# Decawave.net
KiCad netlist of a schematic drawn in Altium Designer
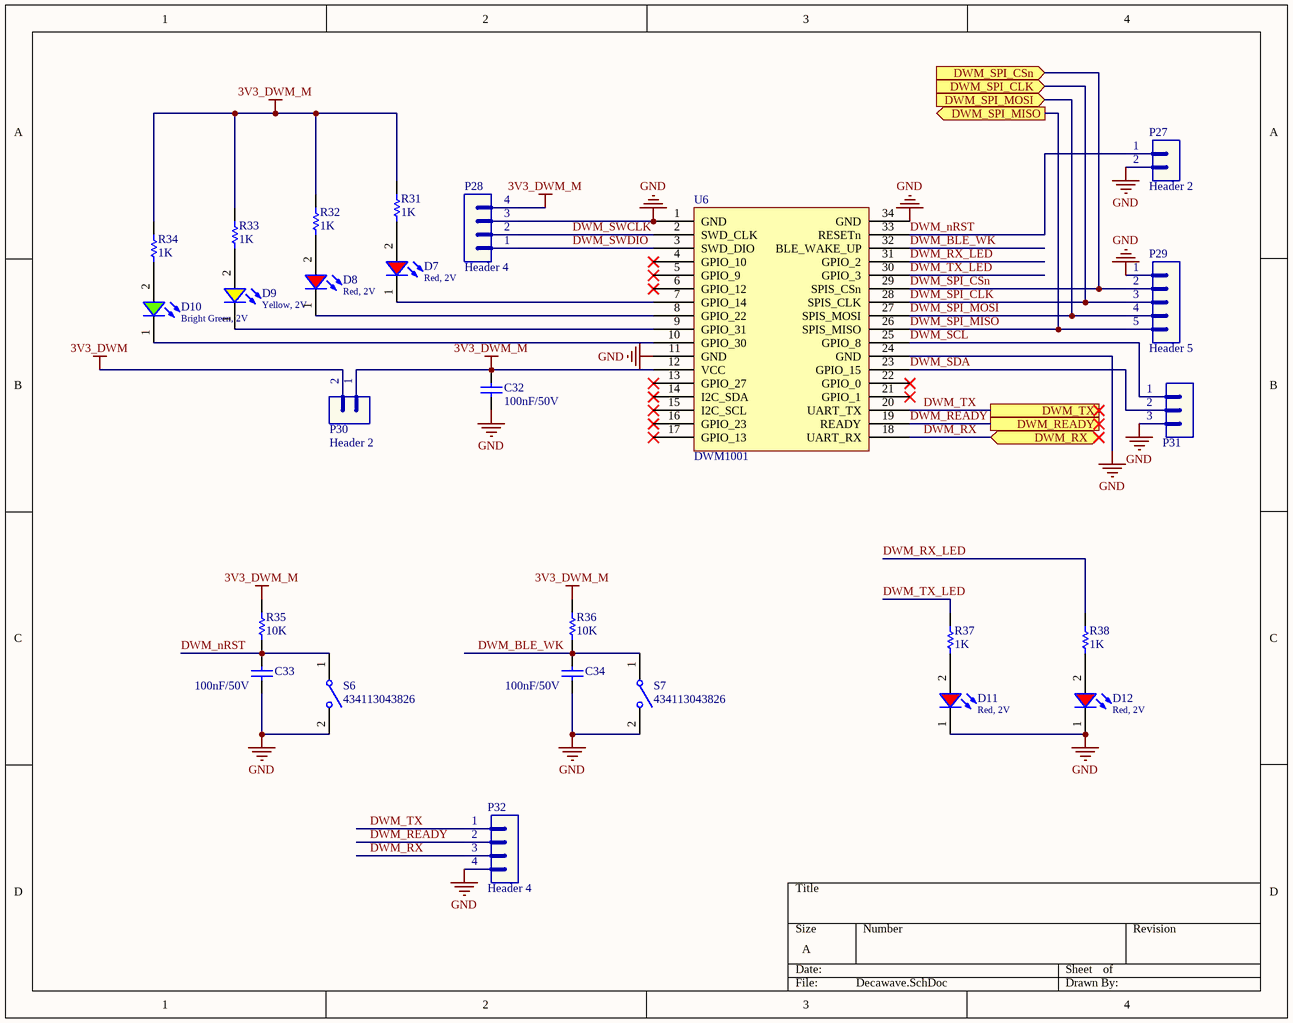
[diagram p0: Decawave.SchDoc]

(export (version "E")
  (design (tool "Eeschema 10.0.6"))
  (components
    (comp (ref "C32")
      (value "100nF/50V")
      (footprint "CAP-SM-0805")
      (description "CAP CER 0.1UF 50V Y5V 0805")
      (fields
        (field (name "MANUFACTURER") "Samsung Electro-Mechanics")
        (field (name "MANUFACTURER PART NUMBER") "CL21F104ZBCNNNC")
      )
      (libsource (lib "Capacitor") (part "Cap-100nF-50V-0805"))
    )
    (comp (ref "C33")
      (value "100nF/50V")
      (footprint "CAP-SM-0805")
      (description "CAP CER 0.1UF 50V Y5V 0805")
      (fields
        (field (name "MANUFACTURER") "Samsung Electro-Mechanics")
        (field (name "MANUFACTURER PART NUMBER") "CL21F104ZBCNNNC")
      )
      (libsource (lib "Capacitor") (part "Cap-100nF-50V-0805"))
    )
    (comp (ref "C34")
      (value "100nF/50V")
      (footprint "CAP-SM-0805")
      (description "CAP CER 0.1UF 50V Y5V 0805")
      (fields
        (field (name "MANUFACTURER") "Samsung Electro-Mechanics")
        (field (name "MANUFACTURER PART NUMBER") "CL21F104ZBCNNNC")
      )
      (libsource (lib "Capacitor") (part "Cap-100nF-50V-0805"))
    )
    (comp (ref "D7")
      (value "Red, 2V")
      (footprint "WL-SMCW_0805")
      (description "WL-SMCW SMT Mono-color Chip LED Waterclear, size 0805, Red, 2V, 140deg")
      (fields (field (name "PART NUMBER") "150080RS75000") (field (name "PUBLISHER") "Wurth Elektronik"))
      (libsource (lib "LED_150060BS75000_Altium_WL-SMCW_rev20a") (part "150080RS75000"))
    )
    (comp (ref "D8")
      (value "Red, 2V")
      (footprint "WL-SMCW_0805")
      (description "WL-SMCW SMT Mono-color Chip LED Waterclear, size 0805, Red, 2V, 140deg")
      (fields (field (name "PART NUMBER") "150080RS75000") (field (name "PUBLISHER") "Wurth Elektronik"))
      (libsource (lib "LED_150060BS75000_Altium_WL-SMCW_rev20a") (part "150080RS75000"))
    )
    (comp (ref "D9")
      (value "Yellow, 2V")
      (footprint "WL-SMCW_0805")
      (description "WL-SMCW SMT Mono-color Chip LED Waterclear, size 0805, Yellow, 2V, 140deg")
      (fields (field (name "PART NUMBER") "150080YS75000") (field (name "PUBLISHER") "Wurth Elektronik"))
      (libsource (lib "LED_150060BS75000_Altium_WL-SMCW_rev20a") (part "150080YS75000"))
    )
    (comp (ref "D10")
      (value "Bright Green, 2V")
      (footprint "WL-SMCW_0805")
      (description "WL-SMCW SMT Mono-color Chip LED Waterclear, size 0805, Bright Green, 2V, 140deg")
      (fields (field (name "PART NUMBER") "150080VS75000") (field (name "PUBLISHER") "Wurth Elektronik"))
      (libsource (lib "LED_150060BS75000_Altium_WL-SMCW_rev20a") (part "150080VS75000"))
    )
    (comp (ref "D11")
      (value "Red, 2V")
      (footprint "WL-SMCW_0805")
      (description "WL-SMCW SMT Mono-color Chip LED Waterclear, size 0805, Red, 2V, 140deg")
      (fields (field (name "PART NUMBER") "150080RS75000") (field (name "PUBLISHER") "Wurth Elektronik"))
      (libsource (lib "LED_150060BS75000_Altium_WL-SMCW_rev20a") (part "150080RS75000"))
    )
    (comp (ref "D12")
      (value "Red, 2V")
      (footprint "WL-SMCW_0805")
      (description "WL-SMCW SMT Mono-color Chip LED Waterclear, size 0805, Red, 2V, 140deg")
      (fields (field (name "PART NUMBER") "150080RS75000") (field (name "PUBLISHER") "Wurth Elektronik"))
      (libsource (lib "LED_150060BS75000_Altium_WL-SMCW_rev20a") (part "150080RS75000"))
    )
    (comp (ref "P27")
      (value "Header 2")
      (footprint "JP2")
      (description "Header, 2-Pin")
      (fields (field (name "PUBLISHER") "Altium Limited"))
      (libsource (lib "") (part "Header 2_1"))
    )
    (comp (ref "P28")
      (value "Header 4")
      (footprint "JP4")
      (description "Header, 4-Pin")
      (fields (field (name "PUBLISHER") "Altium Limited"))
      (libsource (lib "Header-connector") (part "Header 4"))
    )
    (comp (ref "P29")
      (value "Header 5")
      (footprint "JP5")
      (description "Header, 5-Pin")
      (fields (field (name "PUBLISHER") "Altium Limited"))
      (libsource (lib "Header-connector") (part "Header 5"))
    )
    (comp (ref "P30")
      (value "Header 2")
      (footprint "JP2")
      (description "Header, 2-Pin")
      (fields (field (name "PUBLISHER") "Altium Limited"))
      (libsource (lib "Header-connector") (part "Header 2"))
    )
    (comp (ref "P31")
      (value "Header 3")
      (footprint "JP3")
      (description "Header, 3-Pin")
      (fields (field (name "PUBLISHER") "Altium Limited"))
      (libsource (lib "Header-connector") (part "Header 3"))
    )
    (comp (ref "P32")
      (value "Header 4")
      (footprint "JP4")
      (description "Header, 4-Pin")
      (fields (field (name "PUBLISHER") "Altium Limited"))
      (libsource (lib "") (part "Header 4_1"))
    )
    (comp (ref "R31")
      (value "1K")
      (footprint "Resistor:RES-SM-0805")
      (description "RES 1K OHM 1% 1/4W 0805")
      (fields
        (field (name "MANUFACTURER") "Stackpole Electronics Inc")
        (field (name "MANUFACTURER PART NUMBER") "RNCP0805FTD1K00")
      )
      (libsource (lib "Resistor") (part "Res-1K-0805"))
    )
    (comp (ref "R32")
      (value "1K")
      (footprint "Resistor:RES-SM-0805")
      (description "RES 1K OHM 1% 1/4W 0805")
      (fields
        (field (name "MANUFACTURER") "Stackpole Electronics Inc")
        (field (name "MANUFACTURER PART NUMBER") "RNCP0805FTD1K00")
      )
      (libsource (lib "Resistor") (part "Res-1K-0805"))
    )
    (comp (ref "R33")
      (value "1K")
      (footprint "Resistor:RES-SM-0805")
      (description "RES 1K OHM 1% 1/4W 0805")
      (fields
        (field (name "MANUFACTURER") "Stackpole Electronics Inc")
        (field (name "MANUFACTURER PART NUMBER") "RNCP0805FTD1K00")
      )
      (libsource (lib "Resistor") (part "Res-1K-0805"))
    )
    (comp (ref "R34")
      (value "1K")
      (footprint "Resistor:RES-SM-0805")
      (description "RES 1K OHM 1% 1/4W 0805")
      (fields
        (field (name "MANUFACTURER") "Stackpole Electronics Inc")
        (field (name "MANUFACTURER PART NUMBER") "RNCP0805FTD1K00")
      )
      (libsource (lib "Resistor") (part "Res-1K-0805"))
    )
    (comp (ref "R35")
      (value "10K")
      (footprint "Resistor:RES-SM-0805")
      (description "RES 10K OHM 1% 1/4W 0805")
      (fields
        (field (name "MANUFACTURER") "Stackpole Electronics Inc")
        (field (name "MANUFACTURER PART NUMBER") "RNCP0805FTD10K0")
      )
      (libsource (lib "Resistor") (part "Res-10k-0805"))
    )
    (comp (ref "R36")
      (value "10K")
      (footprint "Resistor:RES-SM-0805")
      (description "RES 10K OHM 1% 1/4W 0805")
      (fields
        (field (name "MANUFACTURER") "Stackpole Electronics Inc")
        (field (name "MANUFACTURER PART NUMBER") "RNCP0805FTD10K0")
      )
      (libsource (lib "Resistor") (part "Res-10k-0805"))
    )
    (comp (ref "R37")
      (value "1K")
      (footprint "Resistor:RES-SM-0805")
      (description "RES 1K OHM 1% 1/4W 0805")
      (fields
        (field (name "MANUFACTURER") "Stackpole Electronics Inc")
        (field (name "MANUFACTURER PART NUMBER") "RNCP0805FTD1K00")
      )
      (libsource (lib "Resistor") (part "Res-1K-0805"))
    )
    (comp (ref "R38")
      (value "1K")
      (footprint "Resistor:RES-SM-0805")
      (description "RES 1K OHM 1% 1/4W 0805")
      (fields
        (field (name "MANUFACTURER") "Stackpole Electronics Inc")
        (field (name "MANUFACTURER PART NUMBER") "RNCP0805FTD1K00")
      )
      (libsource (lib "Resistor") (part "Res-1K-0805"))
    )
    (comp (ref "S6")
      (value "434113043826")
      (footprint "434113043826")
      (description "WS-TASV J-Bend SMT Tact Switch 6x3.5mm, height 4.3mm, 260gf")
      (fields (field (name "PUBLISHER") "Wurth Elektronik"))
      (libsource (lib "434113043826_Altium_WS-TASV_rev20a") (part "434113043826"))
    )
    (comp (ref "S7")
      (value "434113043826")
      (footprint "434113043826")
      (description "WS-TASV J-Bend SMT Tact Switch 6x3.5mm, height 4.3mm, 260gf")
      (fields (field (name "PUBLISHER") "Wurth Elektronik"))
      (libsource (lib "434113043826_Altium_WS-TASV_rev20a") (part "434113043826"))
    )
    (comp (ref "U6") (value "DWM1001") (footprint "DWM1001") (libsource (lib "PIFWRoBot") (part "DWM1001")))
  )
  (nets
    (net (code "1") (name "/DWM_BLE_WK") (class "Default")
      (node (ref "C34") (pin "1") (pinfunction "1_1") (pintype "passive"))
      (node (ref "R36") (pin "1") (pinfunction "1_1") (pintype "passive"))
      (node (ref "S7") (pin "1") (pinfunction "1_1") (pintype "passive"))
      (node (ref "U6") (pin "32") (pinfunction "BLE_WAKE_UP_32") (pintype "passive"))
    )
    (net (code "2") (name "/DWM_READY") (class "Default")
      (node (ref "P32") (pin "2") (pinfunction "2_2") (pintype "passive"))
      (node (ref "U6") (pin "19") (pinfunction "READY_19") (pintype "passive"))
    )
    (net (code "3") (name "/DWM_RX") (class "Default")
      (node (ref "P32") (pin "3") (pinfunction "3_3") (pintype "passive"))
      (node (ref "U6") (pin "18") (pinfunction "UART_RX_18") (pintype "passive"))
    )
    (net (code "4") (name "/DWM_RX_LED") (class "Default")
      (node (ref "R38") (pin "2") (pinfunction "2_2") (pintype "passive"))
      (node (ref "U6") (pin "31") (pinfunction "GPIO_2_31") (pintype "passive"))
    )
    (net (code "5") (name "/DWM_SCL") (class "Default")
      (node (ref "P31") (pin "1") (pinfunction "1_1") (pintype "passive"))
      (node (ref "U6") (pin "25") (pinfunction "GPIO_8_25") (pintype "passive"))
    )
    (net (code "6") (name "/DWM_SDA") (class "Default")
      (node (ref "P31") (pin "2") (pinfunction "2_2") (pintype "passive"))
      (node (ref "U6") (pin "23") (pinfunction "GPIO_15_23") (pintype "passive"))
    )
    (net (code "7") (name "/DWM_SPI_CLK") (class "Default")
      (node (ref "P29") (pin "3") (pinfunction "3_3") (pintype "passive"))
      (node (ref "U6") (pin "28") (pinfunction "SPIS_CLK_28") (pintype "passive"))
    )
    (net (code "8") (name "/DWM_SPI_CSn") (class "Default")
      (node (ref "P29") (pin "2") (pinfunction "2_2") (pintype "passive"))
      (node (ref "U6") (pin "29") (pinfunction "SPIS_CSn_29") (pintype "passive"))
    )
    (net (code "9") (name "/DWM_SPI_MISO") (class "Default")
      (node (ref "P29") (pin "5") (pinfunction "5_5") (pintype "passive"))
      (node (ref "U6") (pin "26") (pinfunction "SPIS_MISO_26") (pintype "passive"))
    )
    (net (code "10") (name "/DWM_SPI_MOSI") (class "Default")
      (node (ref "P29") (pin "4") (pinfunction "4_4") (pintype "passive"))
      (node (ref "U6") (pin "27") (pinfunction "SPIS_MOSI_27") (pintype "passive"))
    )
    (net (code "11") (name "/DWM_SWCLK") (class "Default")
      (node (ref "P28") (pin "2") (pinfunction "2_2") (pintype "passive"))
      (node (ref "U6") (pin "2") (pinfunction "SWD_CLK_2") (pintype "passive"))
    )
    (net (code "12") (name "/DWM_SWDIO") (class "Default")
      (node (ref "P28") (pin "1") (pinfunction "1_1") (pintype "passive"))
      (node (ref "U6") (pin "3") (pinfunction "SWD_DIO_3") (pintype "passive"))
    )
    (net (code "13") (name "/DWM_TX") (class "Default")
      (node (ref "P32") (pin "1") (pinfunction "1_1") (pintype "passive"))
      (node (ref "U6") (pin "20") (pinfunction "UART_TX_20") (pintype "passive"))
    )
    (net (code "14") (name "/DWM_TX_LED") (class "Default")
      (node (ref "R37") (pin "2") (pinfunction "2_2") (pintype "passive"))
      (node (ref "U6") (pin "30") (pinfunction "GPIO_3_30") (pintype "passive"))
    )
    (net (code "15") (name "/DWM_nRST") (class "Default")
      (node (ref "C33") (pin "1") (pinfunction "1_1") (pintype "passive"))
      (node (ref "P27") (pin "1") (pinfunction "1_1") (pintype "passive"))
      (node (ref "R35") (pin "1") (pinfunction "1_1") (pintype "passive"))
      (node (ref "S6") (pin "1") (pinfunction "1_1") (pintype "passive"))
      (node (ref "U6") (pin "33") (pinfunction "RESETn_33") (pintype "passive"))
    )
    (net (code "16") (name "3V3_DWM") (class "Default")
      (node (ref "P30") (pin "2") (pinfunction "2_2") (pintype "passive"))
    )
    (net (code "17") (name "3V3_DWM_M") (class "Default")
      (node (ref "C32") (pin "2") (pinfunction "2_2") (pintype "passive"))
      (node (ref "P28") (pin "4") (pinfunction "4_4") (pintype "passive"))
      (node (ref "P30") (pin "1") (pinfunction "1_1") (pintype "passive"))
      (node (ref "R31") (pin "2") (pinfunction "2_2") (pintype "passive"))
      (node (ref "R32") (pin "2") (pinfunction "2_2") (pintype "passive"))
      (node (ref "R33") (pin "2") (pinfunction "2_2") (pintype "passive"))
      (node (ref "R34") (pin "2") (pinfunction "2_2") (pintype "passive"))
      (node (ref "R35") (pin "2") (pinfunction "2_2") (pintype "passive"))
      (node (ref "R36") (pin "2") (pinfunction "2_2") (pintype "passive"))
      (node (ref "U6") (pin "12") (pinfunction "VCC_12") (pintype "passive"))
    )
    (net (code "18") (name "GND") (class "Default")
      (node (ref "C32") (pin "1") (pinfunction "1_1") (pintype "passive"))
      (node (ref "C33") (pin "2") (pinfunction "2_2") (pintype "passive"))
      (node (ref "C34") (pin "2") (pinfunction "2_2") (pintype "passive"))
      (node (ref "D11") (pin "1") (pinfunction "K_1") (pintype "passive"))
      (node (ref "D12") (pin "1") (pinfunction "K_1") (pintype "passive"))
      (node (ref "P27") (pin "2") (pinfunction "2_2") (pintype "passive"))
      (node (ref "P28") (pin "3") (pinfunction "3_3") (pintype "passive"))
      (node (ref "P29") (pin "1") (pinfunction "1_1") (pintype "passive"))
      (node (ref "P31") (pin "3") (pinfunction "3_3") (pintype "passive"))
      (node (ref "P32") (pin "4") (pinfunction "4_4") (pintype "passive"))
      (node (ref "S6") (pin "2") (pinfunction "2_2") (pintype "passive"))
      (node (ref "S7") (pin "2") (pinfunction "2_2") (pintype "passive"))
      (node (ref "U6") (pin "1") (pinfunction "GND_1") (pintype "passive"))
      (node (ref "U6") (pin "11") (pinfunction "GND_11") (pintype "passive"))
      (node (ref "U6") (pin "24") (pinfunction "GND_24") (pintype "passive"))
      (node (ref "U6") (pin "34") (pinfunction "GND_34") (pintype "passive"))
    )
    (net (code "19") (name "Net-(D7-A)") (class "Default")
      (node (ref "D7") (pin "2") (pinfunction "A_2") (pintype "passive"))
      (node (ref "R31") (pin "1") (pinfunction "1_1") (pintype "passive"))
    )
    (net (code "20") (name "Net-(D7-K)") (class "Default")
      (node (ref "D7") (pin "1") (pinfunction "K_1") (pintype "passive"))
      (node (ref "U6") (pin "7") (pinfunction "GPIO_14_7") (pintype "passive"))
    )
    (net (code "21") (name "Net-(D8-A)") (class "Default")
      (node (ref "D8") (pin "2") (pinfunction "A_2") (pintype "passive"))
      (node (ref "R32") (pin "1") (pinfunction "1_1") (pintype "passive"))
    )
    (net (code "22") (name "Net-(D8-K)") (class "Default")
      (node (ref "D8") (pin "1") (pinfunction "K_1") (pintype "passive"))
      (node (ref "U6") (pin "8") (pinfunction "GPIO_22_8") (pintype "passive"))
    )
    (net (code "23") (name "Net-(D9-A)") (class "Default")
      (node (ref "D9") (pin "2") (pinfunction "A_2") (pintype "passive"))
      (node (ref "R33") (pin "1") (pinfunction "1_1") (pintype "passive"))
    )
    (net (code "24") (name "Net-(D9-K)") (class "Default")
      (node (ref "D9") (pin "1") (pinfunction "K_1") (pintype "passive"))
      (node (ref "U6") (pin "9") (pinfunction "GPIO_31_9") (pintype "passive"))
    )
    (net (code "25") (name "Net-(D10-A)") (class "Default")
      (node (ref "D10") (pin "2") (pinfunction "A_2") (pintype "passive"))
      (node (ref "R34") (pin "1") (pinfunction "1_1") (pintype "passive"))
    )
    (net (code "26") (name "Net-(D10-K)") (class "Default")
      (node (ref "D10") (pin "1") (pinfunction "K_1") (pintype "passive"))
      (node (ref "U6") (pin "10") (pinfunction "GPIO_30_10") (pintype "passive"))
    )
    (net (code "27") (name "Net-(D11-A)") (class "Default")
      (node (ref "D11") (pin "2") (pinfunction "A_2") (pintype "passive"))
      (node (ref "R37") (pin "1") (pinfunction "1_1") (pintype "passive"))
    )
    (net (code "28") (name "Net-(D12-A)") (class "Default")
      (node (ref "D12") (pin "2") (pinfunction "A_2") (pintype "passive"))
      (node (ref "R38") (pin "1") (pinfunction "1_1") (pintype "passive"))
    )
    (net (code "29") (name "unconnected-(U6-GPIO_0-Pad22)") (class "Default")
      (node (ref "U6") (pin "22") (pinfunction "GPIO_0_22") (pintype "passive+no_connect"))
    )
    (net (code "30") (name "unconnected-(U6-GPIO_1-Pad21)") (class "Default")
      (node (ref "U6") (pin "21") (pinfunction "GPIO_1_21") (pintype "passive+no_connect"))
    )
    (net (code "31") (name "unconnected-(U6-GPIO_9-Pad5)") (class "Default")
      (node (ref "U6") (pin "5") (pinfunction "GPIO_9_5") (pintype "passive+no_connect"))
    )
    (net (code "32") (name "unconnected-(U6-GPIO_10-Pad4)") (class "Default")
      (node (ref "U6") (pin "4") (pinfunction "GPIO_10_4") (pintype "passive+no_connect"))
    )
    (net (code "33") (name "unconnected-(U6-GPIO_12-Pad6)") (class "Default")
      (node (ref "U6") (pin "6") (pinfunction "GPIO_12_6") (pintype "passive+no_connect"))
    )
    (net (code "34") (name "unconnected-(U6-GPIO_13-Pad17)") (class "Default")
      (node (ref "U6") (pin "17") (pinfunction "GPIO_13_17") (pintype "passive+no_connect"))
    )
    (net (code "35") (name "unconnected-(U6-GPIO_23-Pad16)") (class "Default")
      (node (ref "U6") (pin "16") (pinfunction "GPIO_23_16") (pintype "passive+no_connect"))
    )
    (net (code "36") (name "unconnected-(U6-GPIO_27-Pad13)") (class "Default")
      (node (ref "U6") (pin "13") (pinfunction "GPIO_27_13") (pintype "passive+no_connect"))
    )
    (net (code "37") (name "unconnected-(U6-I2C_SCL-Pad15)") (class "Default")
      (node (ref "U6") (pin "15") (pinfunction "I2C_SCL_15") (pintype "passive+no_connect"))
    )
    (net (code "38") (name "unconnected-(U6-I2C_SDA-Pad14)") (class "Default")
      (node (ref "U6") (pin "14") (pinfunction "I2C_SDA_14") (pintype "passive+no_connect"))
    )
  )
)
